# Smart_LCDplusRTC.net
KiCad netlist of a schematic drawn in EAGLE
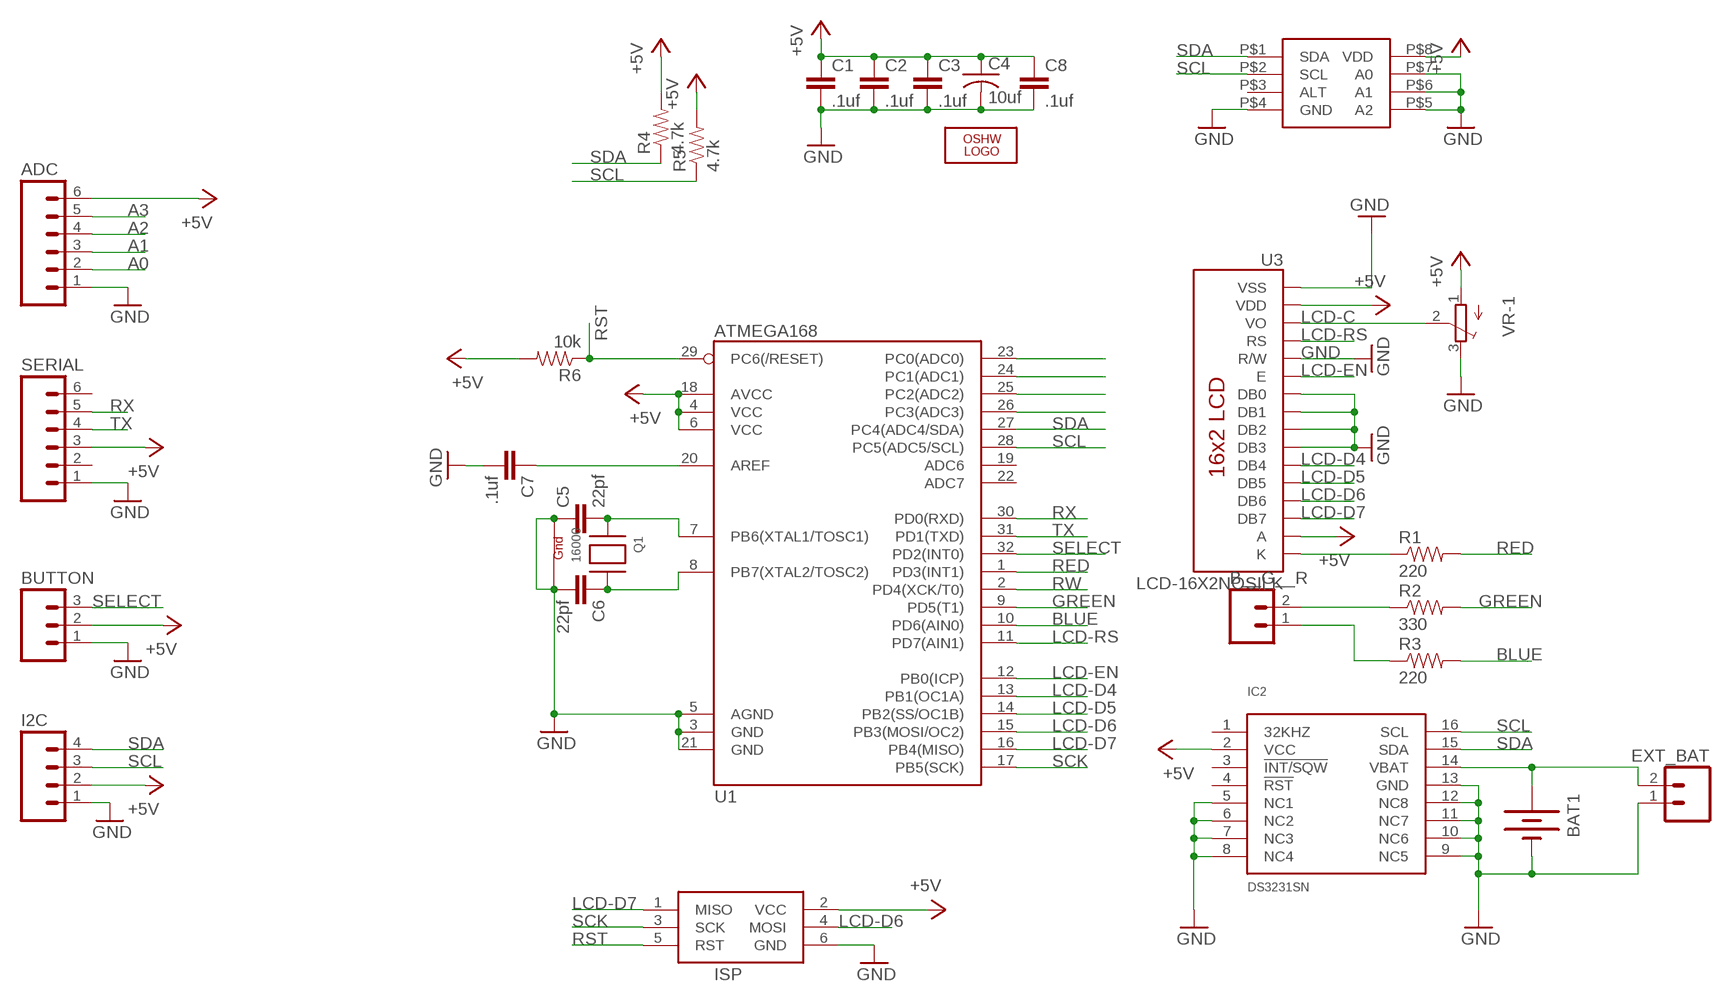
[diagram p0: schematic, sheet 1]

(export (version "E")
  (design (tool "Eeschema 10.0.6"))
  (components
    (comp (ref "ADC")
      (value "M06SIP_LOCK")
      (footprint "eagle-import:1X06-SIP_LOCK")
      (libsource (lib "eagle-import") (part "M06SIP_LOCK"))
    )
    (comp (ref "BAT1")
      (value "BATTERY12MM")
      (footprint "eagle-import:BATTCON_12MM")
      (libsource (lib "eagle-import") (part "BATTERY12MM"))
    )
    (comp (ref "BUTTON")
      (value "M03LOCK")
      (footprint "eagle-import:1X03_LOCK")
      (libsource (lib "eagle-import") (part "M03LOCK"))
    )
    (comp (ref "B__G__R")
      (value "M02LOCK")
      (footprint "eagle-import:1X02_LOCK")
      (libsource (lib "eagle-import") (part "M02LOCK"))
    )
    (comp (ref "C1")
      (value ".1uf")
      (footprint "eagle-import:0805")
      (libsource (lib "eagle-import") (part "CAP0805"))
    )
    (comp (ref "C2")
      (value ".1uf")
      (footprint "eagle-import:0805")
      (libsource (lib "eagle-import") (part "CAP0805"))
    )
    (comp (ref "C3")
      (value ".1uf")
      (footprint "eagle-import:0805")
      (libsource (lib "eagle-import") (part "CAP0805"))
    )
    (comp (ref "C4")
      (value "10uf")
      (footprint "eagle-import:C1206")
      (libsource (lib "eagle-import") (part "C-USC1206"))
    )
    (comp (ref "C5")
      (value "22pf")
      (footprint "eagle-import:0805")
      (libsource (lib "eagle-import") (part "CAP0805"))
    )
    (comp (ref "C6")
      (value "22pf")
      (footprint "eagle-import:0805")
      (libsource (lib "eagle-import") (part "CAP0805"))
    )
    (comp (ref "C7")
      (value ".1uf")
      (footprint "eagle-import:0805")
      (libsource (lib "eagle-import") (part "CAP0805"))
    )
    (comp (ref "C8")
      (value ".1uf")
      (footprint "eagle-import:0805")
      (libsource (lib "eagle-import") (part "CAP0805"))
    )
    (comp (ref "EXT_BAT")
      (value "M02LOCK")
      (footprint "eagle-import:1X02_LOCK")
      (libsource (lib "eagle-import") (part "M02LOCK"))
    )
    (comp (ref "I2C")
      (value "M04LOCK")
      (footprint "eagle-import:1X04_LOCK")
      (libsource (lib "eagle-import") (part "M04LOCK"))
    )
    (comp (ref "IC2")
      (value "DS3231SN")
      (footprint "eagle-import:SO16W")
      (libsource (lib "eagle-import") (part "DS3231SN"))
    )
    (comp (ref "ISP")
      (value "AVRISP-6")
      (footprint "eagle-import:AVRISP")
      (libsource (lib "eagle-import") (part "AVRISP-6"))
    )
    (comp (ref "LOGO2")
      (value "OSHW_LOGO_10MILX0350-NT")
      (footprint "eagle-import:OSHW_10X350_NOTEXT")
      (libsource (lib "eagle-import") (part "OSHW_LOGO_10MILX0350-NT"))
    )
    (comp (ref "Q1")
      (value "16000")
      (footprint "eagle-import:NX3225")
      (libsource (lib "eagle-import") (part "XTAL-4-3225"))
    )
    (comp (ref "R1")
      (value "220")
      (footprint "eagle-import:0805")
      (libsource (lib "eagle-import") (part "RESISTOR0805-RES"))
    )
    (comp (ref "R2")
      (value "330")
      (footprint "eagle-import:0805")
      (libsource (lib "eagle-import") (part "RESISTOR0805-RES"))
    )
    (comp (ref "R3")
      (value "220")
      (footprint "eagle-import:0805")
      (libsource (lib "eagle-import") (part "RESISTOR0805-RES"))
    )
    (comp (ref "R4")
      (value "4.7k")
      (footprint "eagle-import:0805")
      (libsource (lib "eagle-import") (part "RESISTOR0805-RES"))
    )
    (comp (ref "R5")
      (value "4.7k")
      (footprint "eagle-import:0805")
      (libsource (lib "eagle-import") (part "RESISTOR0805-RES"))
    )
    (comp (ref "R6")
      (value "10k")
      (footprint "eagle-import:0805")
      (libsource (lib "eagle-import") (part "RESISTOR0805-RES"))
    )
    (comp (ref "SERIAL")
      (value "M06LOCK")
      (footprint "eagle-import:1X06_LOCK")
      (libsource (lib "eagle-import") (part "M06LOCK"))
    )
    (comp (ref "U$1")
      (value "MCP9808")
      (footprint "eagle-import:MSOP8")
      (libsource (lib "eagle-import") (part "MCP9808"))
    )
    (comp (ref "U1")
      (value "ATMEGA168")
      (footprint "eagle-import:TQFP32-08")
      (libsource (lib "eagle-import") (part "ATMEGA168"))
    )
    (comp (ref "U3")
      (value "LCD-16X2NOSILK")
      (footprint "eagle-import:LCD-16X2_NOSILK")
      (libsource (lib "eagle-import") (part "LCD-16X2NOSILK"))
    )
    (comp (ref "VR-1")
      (value "TRIMPOTTC33X")
      (footprint "eagle-import:TC33X")
      (libsource (lib "eagle-import") (part "TRIMPOTTC33X"))
    )
  )
  (nets
    (net (code "1") (name "+5V") (class "Default")
      (node (ref "ADC") (pin "6") (pinfunction "6_6") (pintype "passive"))
      (node (ref "BUTTON") (pin "2") (pinfunction "2_2") (pintype "passive"))
      (node (ref "C1") (pin "1") (pinfunction "1_1") (pintype "passive"))
      (node (ref "C2") (pin "1") (pinfunction "1_1") (pintype "passive"))
      (node (ref "C3") (pin "1") (pinfunction "1_1") (pintype "passive"))
      (node (ref "C4") (pin "1") (pinfunction "1_1") (pintype "passive"))
      (node (ref "C8") (pin "1") (pinfunction "1_1") (pintype "passive"))
      (node (ref "I2C") (pin "2") (pinfunction "2_2") (pintype "passive"))
      (node (ref "IC2") (pin "2") (pinfunction "VCC_2") (pintype "bidirectional"))
      (node (ref "ISP") (pin "2") (pinfunction "VCC_2") (pintype "power_in"))
      (node (ref "R4") (pin "2") (pinfunction "2_2") (pintype "passive"))
      (node (ref "R5") (pin "2") (pinfunction "2_2") (pintype "passive"))
      (node (ref "R6") (pin "2") (pinfunction "2_2") (pintype "passive"))
      (node (ref "SERIAL") (pin "3") (pinfunction "3_3") (pintype "passive"))
      (node (ref "U$1") (pin "P$8") (pinfunction "VDD_P$8") (pintype "bidirectional"))
      (node (ref "U1") (pin "18") (pinfunction "AVCC_18") (pintype "bidirectional"))
      (node (ref "U1") (pin "4") (pinfunction "VCC_4") (pintype "bidirectional"))
      (node (ref "U1") (pin "6") (pinfunction "VCC_6") (pintype "bidirectional"))
      (node (ref "U3") (pin "15") (pinfunction "A_15") (pintype "power_in"))
      (node (ref "U3") (pin "2") (pinfunction "VDD_2") (pintype "power_in"))
      (node (ref "VR-1") (pin "1") (pinfunction "A_1") (pintype "passive"))
    )
    (net (code "2") (name "/A0") (class "Default")
      (node (ref "ADC") (pin "2") (pinfunction "2_2") (pintype "passive"))
      (node (ref "U1") (pin "23") (pinfunction "PC0(ADC0)_23") (pintype "bidirectional"))
    )
    (net (code "3") (name "/A1") (class "Default")
      (node (ref "ADC") (pin "3") (pinfunction "3_3") (pintype "passive"))
      (node (ref "U1") (pin "24") (pinfunction "PC1(ADC1)_24") (pintype "bidirectional"))
    )
    (net (code "4") (name "/A2") (class "Default")
      (node (ref "ADC") (pin "4") (pinfunction "4_4") (pintype "passive"))
      (node (ref "U1") (pin "25") (pinfunction "PC2(ADC2)_25") (pintype "bidirectional"))
    )
    (net (code "5") (name "/A3") (class "Default")
      (node (ref "ADC") (pin "5") (pinfunction "5_5") (pintype "passive"))
      (node (ref "U1") (pin "26") (pinfunction "PC3(ADC3)_26") (pintype "bidirectional"))
    )
    (net (code "6") (name "/BLUE") (class "Default")
      (node (ref "R3") (pin "2") (pinfunction "2_2") (pintype "passive"))
      (node (ref "U1") (pin "10") (pinfunction "PD6(AIN0)_10") (pintype "bidirectional"))
    )
    (net (code "7") (name "/GREEN") (class "Default")
      (node (ref "R2") (pin "2") (pinfunction "2_2") (pintype "passive"))
      (node (ref "U1") (pin "9") (pinfunction "PD5(T1)_9") (pintype "bidirectional"))
    )
    (net (code "8") (name "/LCD-C") (class "Default")
      (node (ref "U3") (pin "3") (pinfunction "VO_3") (pintype "bidirectional"))
      (node (ref "VR-1") (pin "2") (pinfunction "S_2") (pintype "passive"))
    )
    (net (code "9") (name "/LCD-D4") (class "Default")
      (node (ref "U1") (pin "13") (pinfunction "PB1(OC1A)_13") (pintype "bidirectional"))
      (node (ref "U3") (pin "11") (pinfunction "DB4_11") (pintype "bidirectional"))
    )
    (net (code "10") (name "/LCD-D5") (class "Default")
      (node (ref "U1") (pin "14") (pinfunction "PB2(SS/OC1B)_14") (pintype "bidirectional"))
      (node (ref "U3") (pin "12") (pinfunction "DB5_12") (pintype "bidirectional"))
    )
    (net (code "11") (name "/LCD-D6") (class "Default")
      (node (ref "ISP") (pin "4") (pinfunction "MOSI_4") (pintype "output"))
      (node (ref "U1") (pin "15") (pinfunction "PB3(MOSI/OC2)_15") (pintype "bidirectional"))
      (node (ref "U3") (pin "13") (pinfunction "DB6_13") (pintype "bidirectional"))
    )
    (net (code "12") (name "/LCD-D7") (class "Default")
      (node (ref "ISP") (pin "1") (pinfunction "MISO_1") (pintype "input"))
      (node (ref "U1") (pin "16") (pinfunction "PB4(MISO)_16") (pintype "bidirectional"))
      (node (ref "U3") (pin "14") (pinfunction "DB7_14") (pintype "bidirectional"))
    )
    (net (code "13") (name "/LCD-EN") (class "Default")
      (node (ref "U1") (pin "12") (pinfunction "PB0(ICP)_12") (pintype "bidirectional"))
      (node (ref "U3") (pin "6") (pinfunction "E_6") (pintype "input"))
    )
    (net (code "14") (name "/LCD-RS") (class "Default")
      (node (ref "U1") (pin "11") (pinfunction "PD7(AIN1)_11") (pintype "bidirectional"))
      (node (ref "U3") (pin "4") (pinfunction "RS_4") (pintype "input"))
    )
    (net (code "15") (name "/RED") (class "Default")
      (node (ref "R1") (pin "2") (pinfunction "2_2") (pintype "passive"))
      (node (ref "U1") (pin "1") (pinfunction "PD3(INT1)_1") (pintype "bidirectional"))
    )
    (net (code "16") (name "/RST") (class "Default")
      (node (ref "ISP") (pin "5") (pinfunction "RST_5") (pintype "output"))
      (node (ref "R6") (pin "1") (pinfunction "1_1") (pintype "passive"))
      (node (ref "U1") (pin "29") (pinfunction "PC6(/RESET)_29") (pintype "bidirectional"))
    )
    (net (code "17") (name "/RW") (class "Default")
      (node (ref "U1") (pin "2") (pinfunction "PD4(XCK/T0)_2") (pintype "bidirectional"))
    )
    (net (code "18") (name "/RX") (class "Default")
      (node (ref "SERIAL") (pin "5") (pinfunction "5_5") (pintype "passive"))
      (node (ref "U1") (pin "30") (pinfunction "PD0(RXD)_30") (pintype "bidirectional"))
    )
    (net (code "19") (name "/SCK") (class "Default")
      (node (ref "ISP") (pin "3") (pinfunction "SCK_3") (pintype "output"))
      (node (ref "U1") (pin "17") (pinfunction "PB5(SCK)_17") (pintype "bidirectional"))
    )
    (net (code "20") (name "/SCL") (class "Default")
      (node (ref "I2C") (pin "3") (pinfunction "3_3") (pintype "passive"))
      (node (ref "IC2") (pin "16") (pinfunction "SCL_16") (pintype "bidirectional"))
      (node (ref "R5") (pin "1") (pinfunction "1_1") (pintype "passive"))
      (node (ref "U$1") (pin "P$2") (pinfunction "SCL_P$2") (pintype "bidirectional"))
      (node (ref "U1") (pin "28") (pinfunction "PC5(ADC5/SCL)_28") (pintype "bidirectional"))
    )
    (net (code "21") (name "/SDA") (class "Default")
      (node (ref "I2C") (pin "4") (pinfunction "4_4") (pintype "passive"))
      (node (ref "IC2") (pin "15") (pinfunction "SDA_15") (pintype "bidirectional"))
      (node (ref "R4") (pin "1") (pinfunction "1_1") (pintype "passive"))
      (node (ref "U$1") (pin "P$1") (pinfunction "SDA_P$1") (pintype "bidirectional"))
      (node (ref "U1") (pin "27") (pinfunction "PC4(ADC4/SDA)_27") (pintype "bidirectional"))
    )
    (net (code "22") (name "/SELECT") (class "Default")
      (node (ref "BUTTON") (pin "3") (pinfunction "3_3") (pintype "passive"))
      (node (ref "U1") (pin "32") (pinfunction "PD2(INT0)_32") (pintype "bidirectional"))
    )
    (net (code "23") (name "/TX") (class "Default")
      (node (ref "SERIAL") (pin "4") (pinfunction "4_4") (pintype "passive"))
      (node (ref "U1") (pin "31") (pinfunction "PD1(TXD)_31") (pintype "bidirectional"))
    )
    (net (code "24") (name "GND") (class "Default")
      (node (ref "ADC") (pin "1") (pinfunction "1_1") (pintype "passive"))
      (node (ref "BAT1") (pin "GND") (pinfunction "-_GND") (pintype "power_in"))
      (node (ref "BUTTON") (pin "1") (pinfunction "1_1") (pintype "passive"))
      (node (ref "C1") (pin "2") (pinfunction "2_2") (pintype "passive"))
      (node (ref "C2") (pin "2") (pinfunction "2_2") (pintype "passive"))
      (node (ref "C3") (pin "2") (pinfunction "2_2") (pintype "passive"))
      (node (ref "C4") (pin "2") (pinfunction "2_2") (pintype "passive"))
      (node (ref "C5") (pin "1") (pinfunction "1_1") (pintype "passive"))
      (node (ref "C6") (pin "2") (pinfunction "2_2") (pintype "passive"))
      (node (ref "C7") (pin "2") (pinfunction "2_2") (pintype "passive"))
      (node (ref "C8") (pin "2") (pinfunction "2_2") (pintype "passive"))
      (node (ref "EXT_BAT") (pin "1") (pinfunction "1_1") (pintype "passive"))
      (node (ref "I2C") (pin "1") (pinfunction "1_1") (pintype "passive"))
      (node (ref "IC2") (pin "10") (pinfunction "NC6_10") (pintype "bidirectional"))
      (node (ref "IC2") (pin "11") (pinfunction "NC7_11") (pintype "bidirectional"))
      (node (ref "IC2") (pin "12") (pinfunction "NC8_12") (pintype "bidirectional"))
      (node (ref "IC2") (pin "13") (pinfunction "GND_13") (pintype "bidirectional"))
      (node (ref "IC2") (pin "5") (pinfunction "NC1_5") (pintype "bidirectional"))
      (node (ref "IC2") (pin "6") (pinfunction "NC2_6") (pintype "bidirectional"))
      (node (ref "IC2") (pin "7") (pinfunction "NC3_7") (pintype "bidirectional"))
      (node (ref "IC2") (pin "8") (pinfunction "NC4_8") (pintype "bidirectional"))
      (node (ref "IC2") (pin "9") (pinfunction "NC5_9") (pintype "bidirectional"))
      (node (ref "ISP") (pin "6") (pinfunction "GND_6") (pintype "power_in"))
      (node (ref "Q1") (pin "1") (pinfunction "G1_1") (pintype "power_in"))
      (node (ref "Q1") (pin "3") (pinfunction "G2_3") (pintype "power_in"))
      (node (ref "SERIAL") (pin "1") (pinfunction "1_1") (pintype "passive"))
      (node (ref "U$1") (pin "P$4") (pinfunction "GND_P$4") (pintype "bidirectional"))
      (node (ref "U$1") (pin "P$5") (pinfunction "A2_P$5") (pintype "bidirectional"))
      (node (ref "U$1") (pin "P$6") (pinfunction "A1_P$6") (pintype "bidirectional"))
      (node (ref "U$1") (pin "P$7") (pinfunction "A0_P$7") (pintype "bidirectional"))
      (node (ref "U1") (pin "21") (pinfunction "GND_21") (pintype "bidirectional"))
      (node (ref "U1") (pin "3") (pinfunction "GND_3") (pintype "bidirectional"))
      (node (ref "U1") (pin "5") (pinfunction "AGND_5") (pintype "bidirectional"))
      (node (ref "U3") (pin "1") (pinfunction "VSS_1") (pintype "power_in"))
      (node (ref "U3") (pin "10") (pinfunction "DB3_10") (pintype "bidirectional"))
      (node (ref "U3") (pin "5") (pinfunction "R/W_5") (pintype "input"))
      (node (ref "U3") (pin "7") (pinfunction "DB0_7") (pintype "bidirectional"))
      (node (ref "U3") (pin "8") (pinfunction "DB1_8") (pintype "bidirectional"))
      (node (ref "U3") (pin "9") (pinfunction "DB2_9") (pintype "bidirectional"))
      (node (ref "VR-1") (pin "3") (pinfunction "E_3") (pintype "passive"))
    )
    (net (code "25") (name "Net-(BAT1-+)") (class "Default")
      (node (ref "BAT1") (pin "PWR@1") (pinfunction "+_PWR@1") (pintype "power_in"))
      (node (ref "EXT_BAT") (pin "2") (pinfunction "2_2") (pintype "passive"))
      (node (ref "IC2") (pin "14") (pinfunction "VBAT_14") (pintype "bidirectional"))
    )
    (net (code "26") (name "Net-(B__G__R-Pad1)") (class "Default")
      (node (ref "B__G__R") (pin "1") (pinfunction "1_1") (pintype "passive"))
      (node (ref "R3") (pin "1") (pinfunction "1_1") (pintype "passive"))
    )
    (net (code "27") (name "Net-(B__G__R-Pad2)") (class "Default")
      (node (ref "B__G__R") (pin "2") (pinfunction "2_2") (pintype "passive"))
      (node (ref "R2") (pin "1") (pinfunction "1_1") (pintype "passive"))
    )
    (net (code "28") (name "Net-(Q1-X1)") (class "Default")
      (node (ref "C5") (pin "2") (pinfunction "2_2") (pintype "passive"))
      (node (ref "Q1") (pin "2") (pinfunction "X1_2") (pintype "bidirectional"))
      (node (ref "U1") (pin "7") (pinfunction "PB6(XTAL1/TOSC1)_7") (pintype "bidirectional"))
    )
    (net (code "29") (name "Net-(Q1-X2)") (class "Default")
      (node (ref "C6") (pin "1") (pinfunction "1_1") (pintype "passive"))
      (node (ref "Q1") (pin "4") (pinfunction "X2_4") (pintype "bidirectional"))
      (node (ref "U1") (pin "8") (pinfunction "PB7(XTAL2/TOSC2)_8") (pintype "bidirectional"))
    )
    (net (code "30") (name "Net-(U1-AREF)") (class "Default")
      (node (ref "C7") (pin "1") (pinfunction "1_1") (pintype "passive"))
      (node (ref "U1") (pin "20") (pinfunction "AREF_20") (pintype "bidirectional"))
    )
    (net (code "31") (name "Net-(U3-K)") (class "Default")
      (node (ref "R1") (pin "1") (pinfunction "1_1") (pintype "passive"))
      (node (ref "U3") (pin "16") (pinfunction "K_16") (pintype "power_in"))
    )
    (net (code "32") (name "unconnected-(IC2-32KHZ-Pad1)") (class "Default")
      (node (ref "IC2") (pin "1") (pinfunction "32KHZ_1") (pintype "bidirectional"))
    )
    (net (code "33") (name "unconnected-(IC2-~{INT{slash}SQW}-Pad3)") (class "Default")
      (node (ref "IC2") (pin "3") (pinfunction "~{INT/SQW}_3") (pintype "bidirectional"))
    )
    (net (code "34") (name "unconnected-(IC2-~{RST}-Pad4)") (class "Default")
      (node (ref "IC2") (pin "4") (pinfunction "~{RST}_4") (pintype "bidirectional"))
    )
    (net (code "35") (name "unconnected-(SERIAL-Pad2)") (class "Default")
      (node (ref "SERIAL") (pin "2") (pinfunction "2_2") (pintype "passive"))
    )
    (net (code "36") (name "unconnected-(SERIAL-Pad6)") (class "Default")
      (node (ref "SERIAL") (pin "6") (pinfunction "6_6") (pintype "passive"))
    )
    (net (code "37") (name "unconnected-(U$1-ALT-PadP$3)") (class "Default")
      (node (ref "U$1") (pin "P$3") (pinfunction "ALT_P$3") (pintype "bidirectional"))
    )
    (net (code "38") (name "unconnected-(U1-ADC6-Pad19)") (class "Default")
      (node (ref "U1") (pin "19") (pinfunction "ADC6_19") (pintype "bidirectional"))
    )
    (net (code "39") (name "unconnected-(U1-ADC7-Pad22)") (class "Default")
      (node (ref "U1") (pin "22") (pinfunction "ADC7_22") (pintype "bidirectional"))
    )
  )
)
